# TESTOMATIC-v1_0.net
KiCad netlist of a schematic drawn in EAGLE
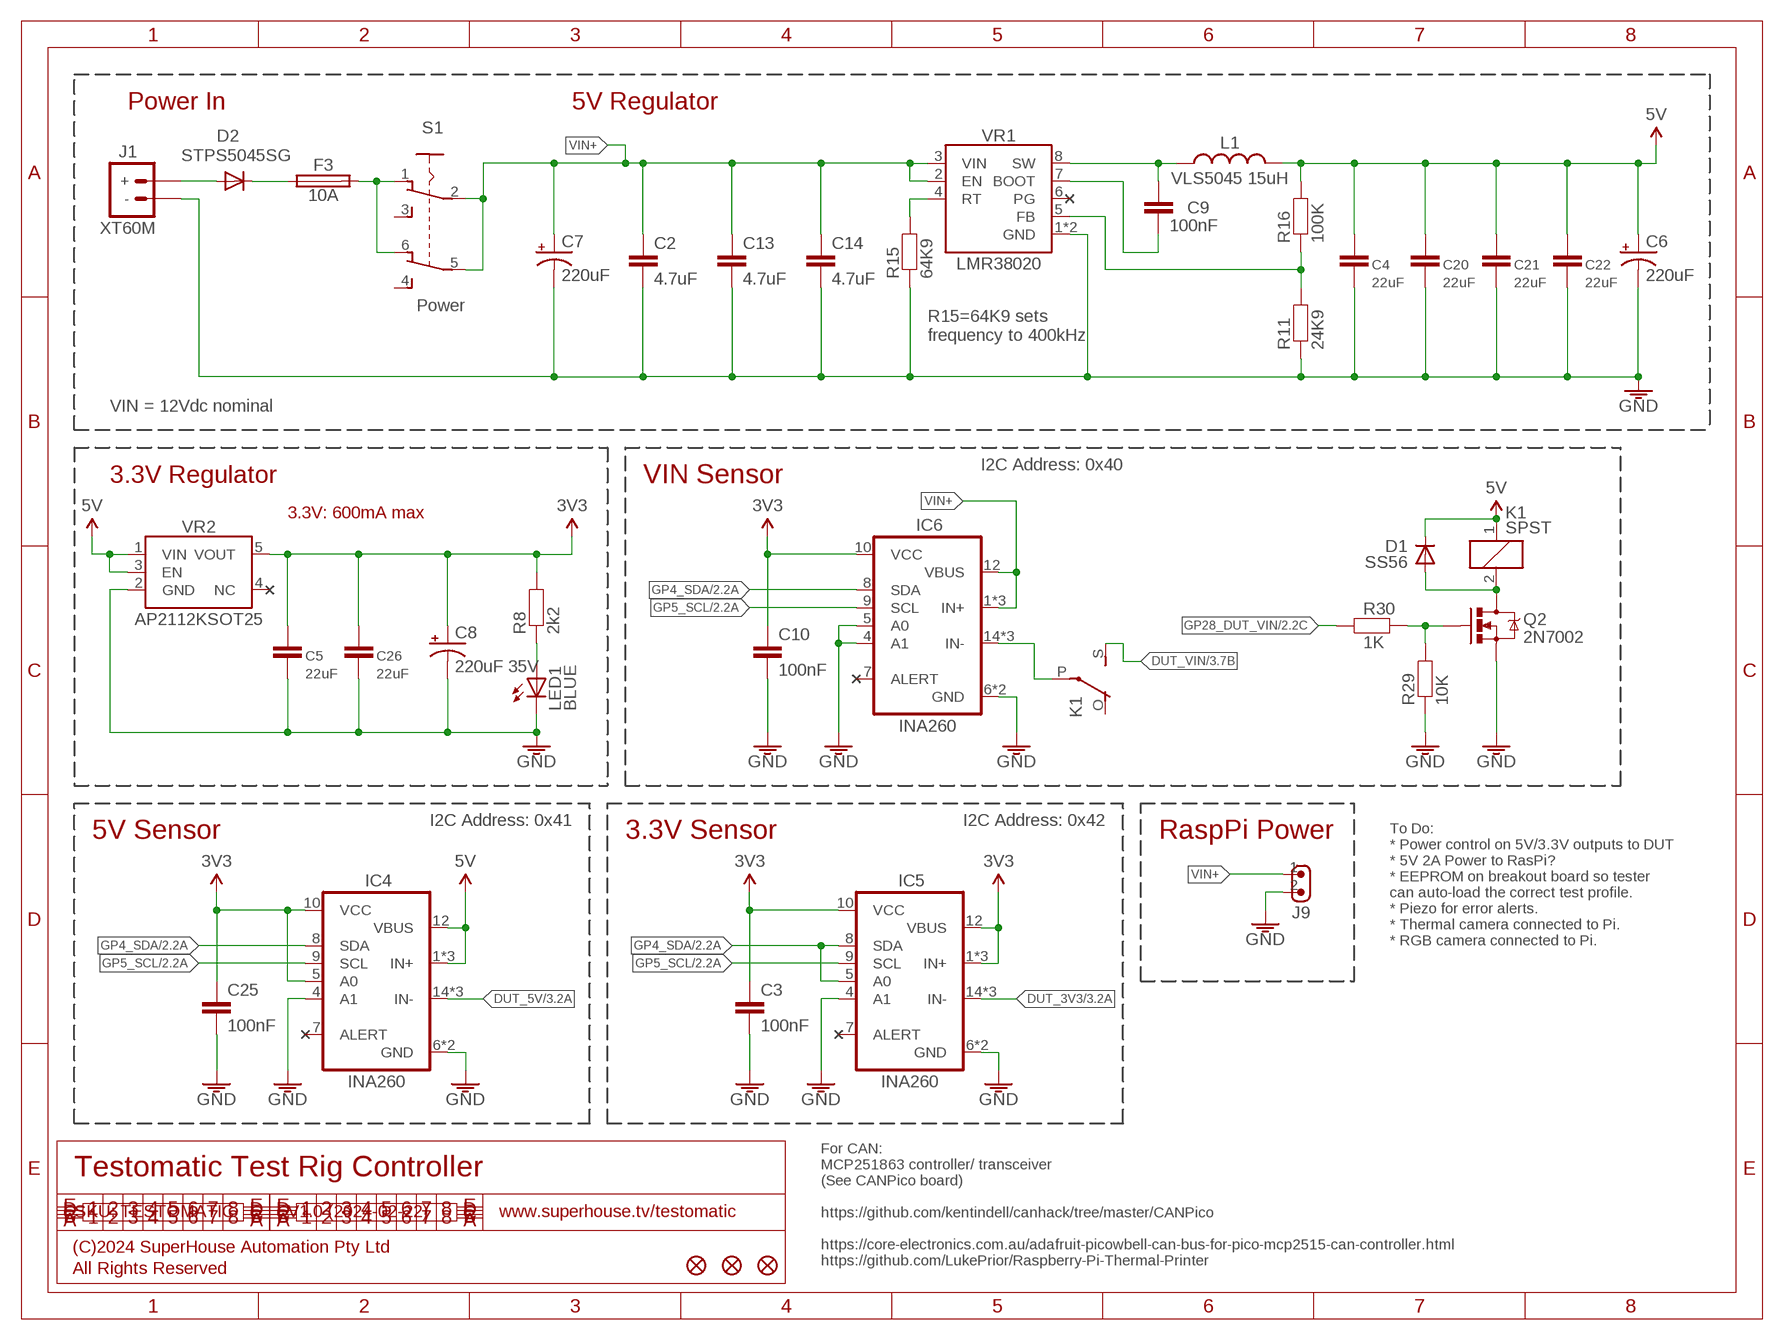
[diagram p0: schematic, sheet 1]
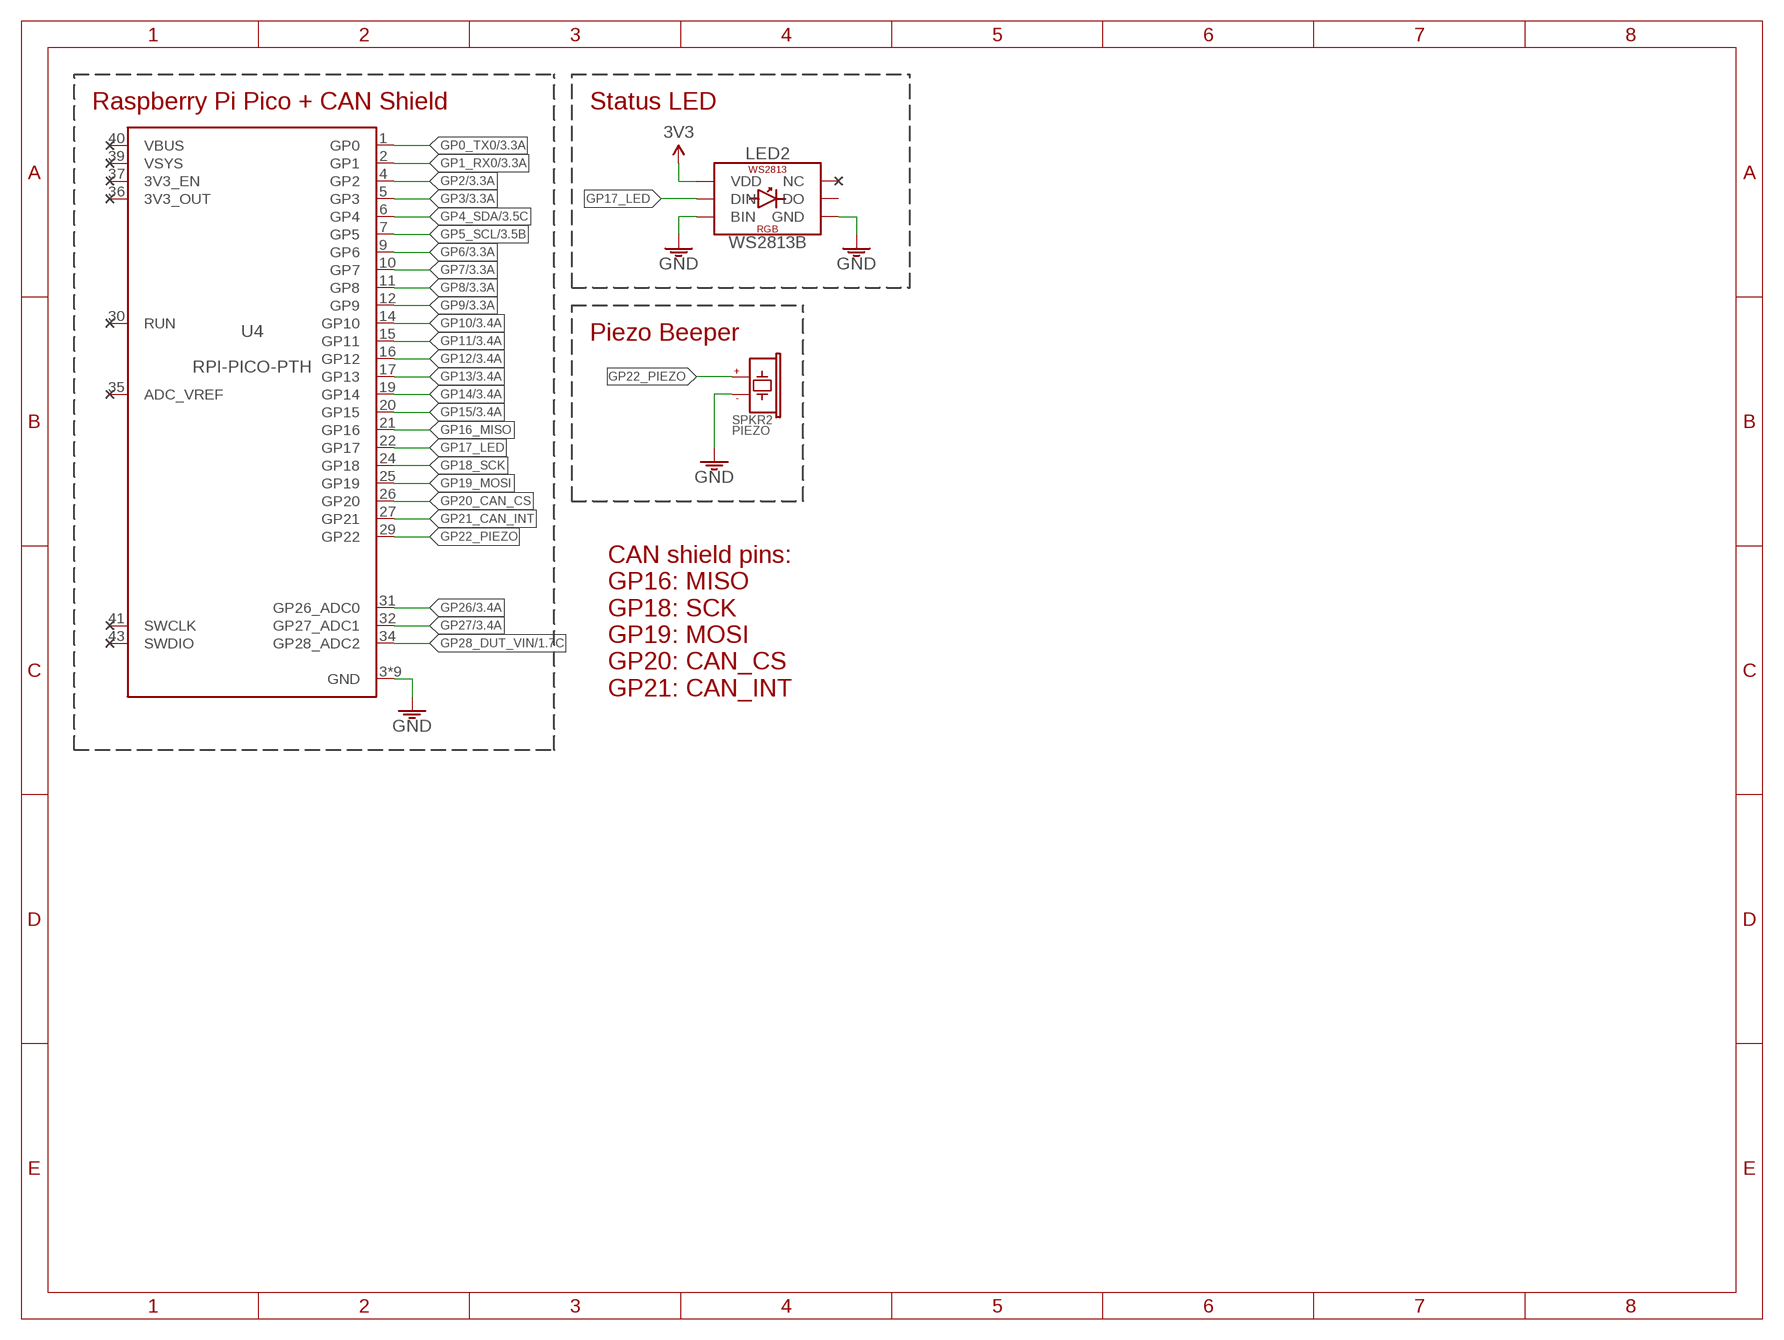
[diagram p1: schematic, sheet 2]
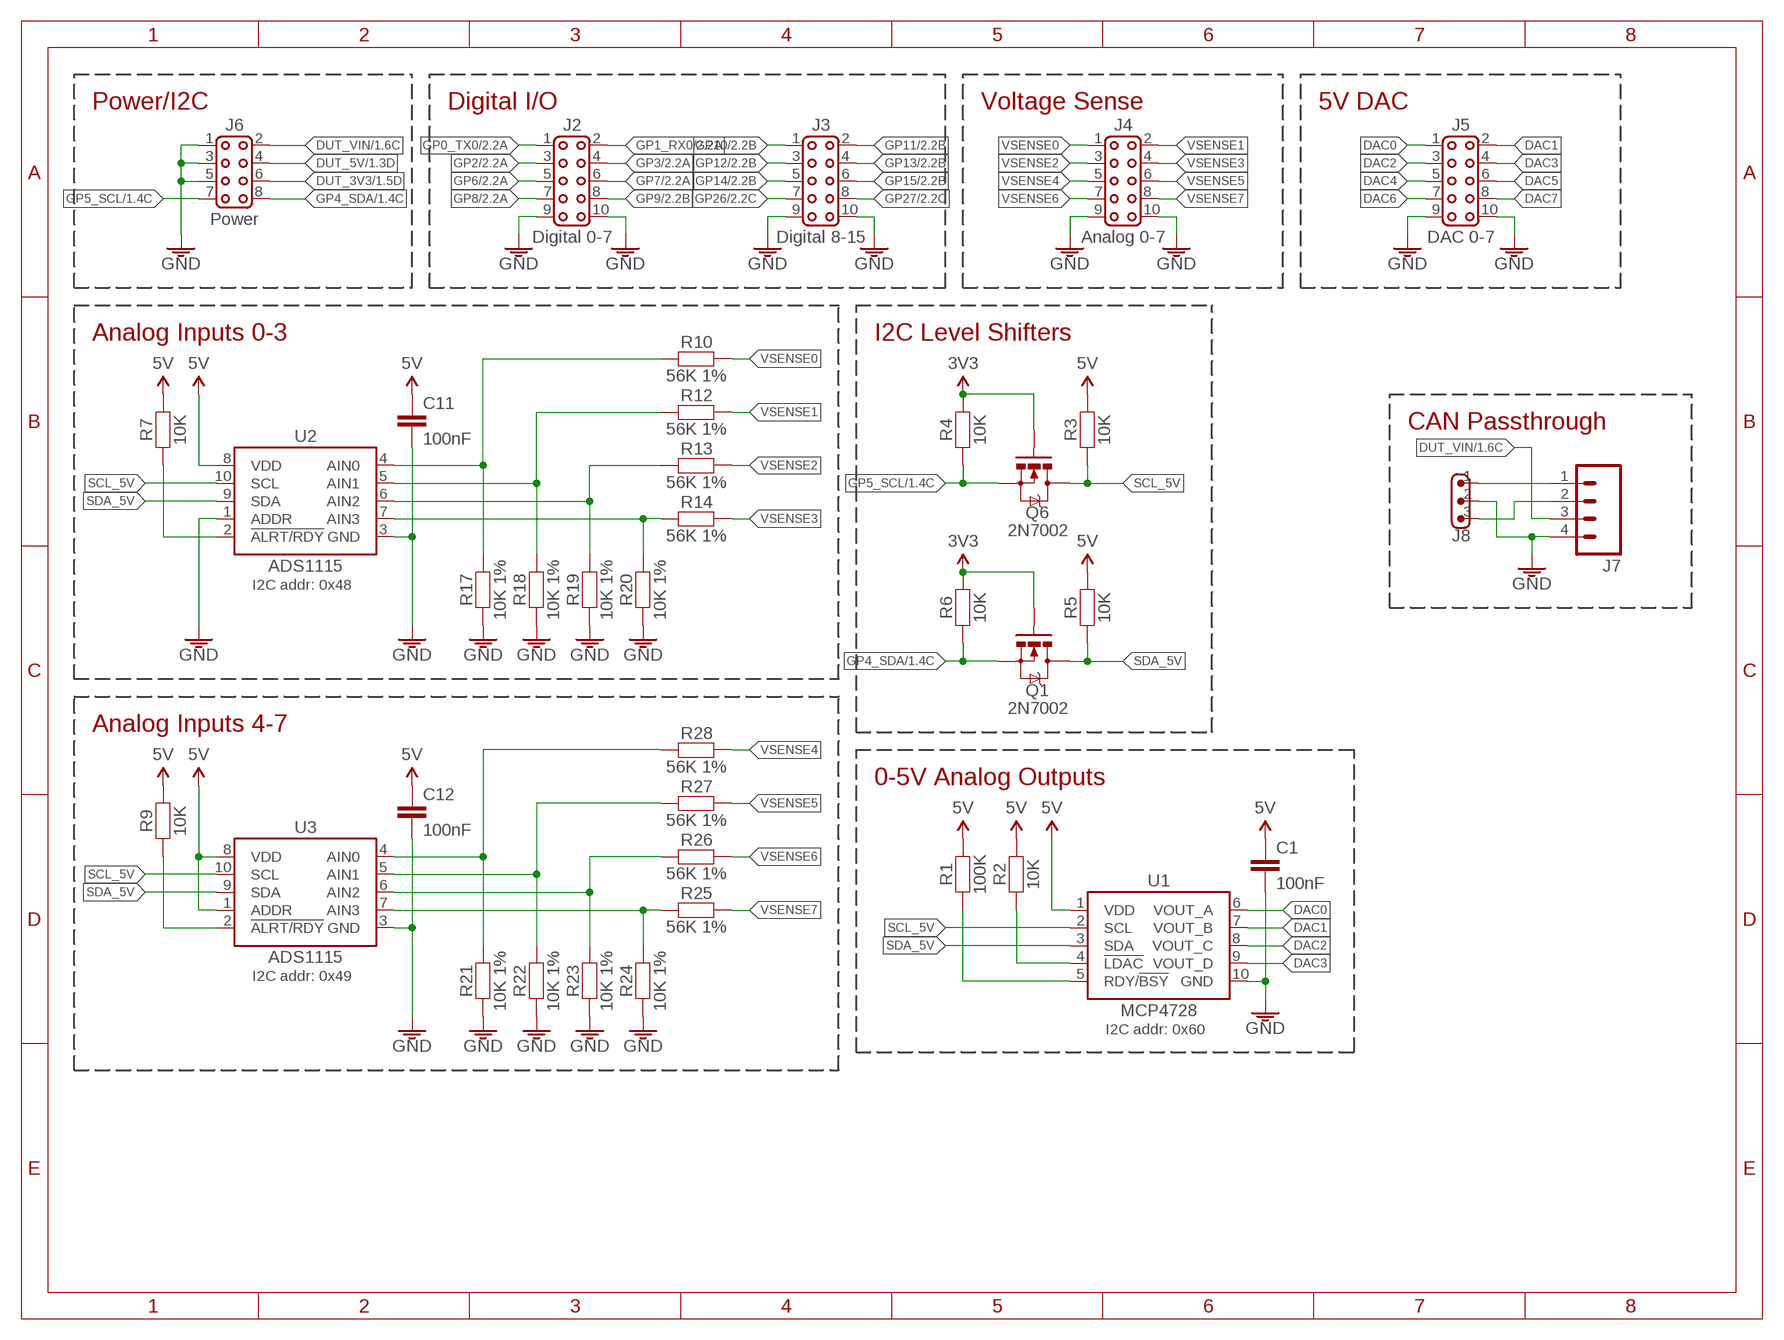
[diagram p2: schematic, sheet 3]

(export (version "E")
  (design (tool "Eeschema 10.0.6"))
  (components
    (comp (ref "C2")
      (value "4.7uF")
      (footprint "eagle-import:C1206")
      (libsource (lib "eagle-import") (part "CAP1206"))
    )
    (comp (ref "C3")
      (value "100nF")
      (footprint "eagle-import:C0603")
      (libsource (lib "eagle-import") (part "CAP0603"))
    )
    (comp (ref "C4")
      (value "22uF")
      (footprint "eagle-import:C0805")
      (libsource (lib "eagle-import") (part "CAP0805"))
    )
    (comp (ref "C5")
      (value "22uF")
      (footprint "eagle-import:C0805")
      (libsource (lib "eagle-import") (part "CAP0805"))
    )
    (comp (ref "C6")
      (value "220uF")
      (footprint "eagle-import:PANASONIC_G")
      (libsource (lib "eagle-import") (part "CAP_POLG"))
    )
    (comp (ref "C7")
      (value "220uF")
      (footprint "eagle-import:PANASONIC_G")
      (libsource (lib "eagle-import") (part "CAP_POLG"))
    )
    (comp (ref "C8")
      (value "220uF 35V")
      (footprint "eagle-import:PANASONIC_G")
      (libsource (lib "eagle-import") (part "CAP_POLG"))
    )
    (comp (ref "C9")
      (value "100nF")
      (footprint "eagle-import:C0603")
      (libsource (lib "eagle-import") (part "CAP0603"))
    )
    (comp (ref "C10")
      (value "100nF")
      (footprint "eagle-import:C0603")
      (libsource (lib "eagle-import") (part "CAP0603"))
    )
    (comp (ref "C13")
      (value "4.7uF")
      (footprint "eagle-import:C1206")
      (libsource (lib "eagle-import") (part "CAP1206"))
    )
    (comp (ref "C14")
      (value "4.7uF")
      (footprint "eagle-import:C1206")
      (libsource (lib "eagle-import") (part "CAP1206"))
    )
    (comp (ref "C20")
      (value "22uF")
      (footprint "eagle-import:C0805")
      (libsource (lib "eagle-import") (part "CAP0805"))
    )
    (comp (ref "C21")
      (value "22uF")
      (footprint "eagle-import:C0805")
      (libsource (lib "eagle-import") (part "CAP0805"))
    )
    (comp (ref "C22")
      (value "22uF")
      (footprint "eagle-import:C0805")
      (libsource (lib "eagle-import") (part "CAP0805"))
    )
    (comp (ref "C25")
      (value "100nF")
      (footprint "eagle-import:C0603")
      (libsource (lib "eagle-import") (part "CAP0603"))
    )
    (comp (ref "C26")
      (value "22uF")
      (footprint "eagle-import:C0805")
      (libsource (lib "eagle-import") (part "CAP0805"))
    )
    (comp (ref "D1")
      (value "SS56")
      (footprint "eagle-import:SMA-DIODE")
      (libsource (lib "eagle-import") (part "DIODESMA"))
    )
    (comp (ref "D2")
      (value "STPS5045SG")
      (footprint "eagle-import:D2PACK")
      (libsource (lib "eagle-import") (part "DIODE-D2PAK"))
    )
    (comp (ref "F3")
      (value "10A")
      (footprint "eagle-import:MCCQ-122")
      (libsource (lib "eagle-import") (part "FUSE-MCCQ"))
    )
    (comp (ref "FID1")
      (value "FIDUCIAL1X2.5")
      (footprint "eagle-import:FIDUCIAL-1X2.5")
      (libsource (lib "eagle-import") (part "FIDUCIAL1X2.5"))
    )
    (comp (ref "FID2")
      (value "FIDUCIAL1X2.5")
      (footprint "eagle-import:FIDUCIAL-1X2.5")
      (libsource (lib "eagle-import") (part "FIDUCIAL1X2.5"))
    )
    (comp (ref "FID3")
      (value "FIDUCIAL1X2.5")
      (footprint "eagle-import:FIDUCIAL-1X2.5")
      (libsource (lib "eagle-import") (part "FIDUCIAL1X2.5"))
    )
    (comp (ref "IC4")
      (value "INA260")
      (footprint "eagle-import:TSSOP-16")
      (libsource (lib "eagle-import") (part "INA260"))
    )
    (comp (ref "IC5")
      (value "INA260")
      (footprint "eagle-import:TSSOP-16")
      (libsource (lib "eagle-import") (part "INA260"))
    )
    (comp (ref "IC6")
      (value "INA260")
      (footprint "eagle-import:TSSOP-16")
      (libsource (lib "eagle-import") (part "INA260"))
    )
    (comp (ref "J1")
      (value "XT60M")
      (footprint "eagle-import:XT60PW-M")
      (libsource (lib "eagle-import") (part "XTXX-60M"))
    )
    (comp (ref "J9")
      (value "M02-SCREW-3.81MM-VERT")
      (footprint "eagle-import:SCREWTERMINAL-3.81MM-VERT-2")
      (libsource (lib "eagle-import") (part "M02-SCREW-3.81MM-VERT"))
    )
    (comp (ref "K1")
      (value "SPST")
      (footprint "eagle-import:G5LE")
      (libsource (lib "eagle-import") (part "SPST"))
    )
    (comp (ref "L1")
      (value "VLS5045 15uH")
      (footprint "eagle-import:INDUCTOR-5045")
      (libsource (lib "eagle-import") (part "INDUCTOR-5045"))
    )
    (comp (ref "LED1")
      (value "BLUE")
      (footprint "eagle-import:LED-0603")
      (libsource (lib "eagle-import") (part "LED0603"))
    )
    (comp (ref "Q2")
      (value "2N7002")
      (footprint "eagle-import:SOT23-3")
      (libsource (lib "eagle-import") (part "MOSFET-NCHANNEL-233"))
    )
    (comp (ref "R8")
      (value "2k2")
      (footprint "eagle-import:R0603")
      (libsource (lib "eagle-import") (part "RESISTOR0603"))
    )
    (comp (ref "R11")
      (value "24K9")
      (footprint "eagle-import:R0603")
      (libsource (lib "eagle-import") (part "RESISTOR0603"))
    )
    (comp (ref "R15")
      (value "64K9")
      (footprint "eagle-import:R0603")
      (libsource (lib "eagle-import") (part "RESISTOR0603"))
    )
    (comp (ref "R16")
      (value "100K")
      (footprint "eagle-import:R0603")
      (libsource (lib "eagle-import") (part "RESISTOR0603"))
    )
    (comp (ref "R29")
      (value "10K")
      (footprint "eagle-import:R0603")
      (libsource (lib "eagle-import") (part "RESISTOR0603"))
    )
    (comp (ref "R30")
      (value "1K")
      (footprint "eagle-import:R0603")
      (libsource (lib "eagle-import") (part "RESISTOR0603"))
    )
    (comp (ref "S1")
      (value "Power")
      (footprint "eagle-import:7201SD9AV2BE")
      (libsource (lib "eagle-import") (part "SWITCH-DPDT3"))
    )
    (comp (ref "VR1")
      (value "LMR38020")
      (footprint "eagle-import:HSOIC8")
      (libsource (lib "eagle-import") (part "LMR38010"))
    )
    (comp (ref "VR2")
      (value "AP2112KSOT25")
      (footprint "eagle-import:SOT23-5")
      (libsource (lib "eagle-import") (part "AP2112KSOT25"))
    )
    (comp (ref "LED2")
      (value "WS2813B")
      (footprint "eagle-import:WS2813")
      (libsource (lib "eagle-import") (part "WS2813-5050"))
    )
    (comp (ref "SPKR2")
      (value "PIEZO")
      (footprint "eagle-import:PIEZO-9.6X9.6-SMT")
      (libsource (lib "eagle-import") (part "PIEZOPOLARISED-SMT"))
    )
    (comp (ref "U4")
      (value "RPI-PICO-PTH")
      (footprint "eagle-import:PICO-PTH")
      (libsource (lib "eagle-import") (part "RPI-PICO-PTH"))
    )
    (comp (ref "C1")
      (value "100nF")
      (footprint "eagle-import:C0603")
      (libsource (lib "eagle-import") (part "CAP0603"))
    )
    (comp (ref "C11")
      (value "100nF")
      (footprint "eagle-import:C0603")
      (libsource (lib "eagle-import") (part "CAP0603"))
    )
    (comp (ref "C12")
      (value "100nF")
      (footprint "eagle-import:C0603")
      (libsource (lib "eagle-import") (part "CAP0603"))
    )
    (comp (ref "J2")
      (value "Digital 0-7")
      (footprint "eagle-import:2X05-2.54-SHROUDED")
      (libsource (lib "eagle-import") (part "M02X5-SHROUDED"))
    )
    (comp (ref "J3")
      (value "Digital 8-15")
      (footprint "eagle-import:2X05-2.54-SHROUDED")
      (libsource (lib "eagle-import") (part "M02X5-SHROUDED"))
    )
    (comp (ref "J4")
      (value "Analog 0-7")
      (footprint "eagle-import:2X05-2.54-SHROUDED")
      (libsource (lib "eagle-import") (part "M02X5-SHROUDED"))
    )
    (comp (ref "J5")
      (value "DAC 0-7")
      (footprint "eagle-import:2X05-2.54-SHROUDED")
      (libsource (lib "eagle-import") (part "M02X5-SHROUDED"))
    )
    (comp (ref "J6")
      (value "Power")
      (footprint "eagle-import:2X04-2.54-SHROUDED")
      (libsource (lib "eagle-import") (part "M02X4-SHROUD"))
    )
    (comp (ref "J7")
      (value "M04-SCREW-3.81MM-VERT-PLUG")
      (footprint "eagle-import:SCREWTERMINAL-3.81MM-VERT-4")
      (libsource (lib "eagle-import") (part "M04-SCREW-3.81MM-VERT-PLUG"))
    )
    (comp (ref "J8")
      (value "M03-SCREW-3.5MM")
      (footprint "eagle-import:SCREWTERMINAL-3.5MM-3")
      (libsource (lib "eagle-import") (part "M03-SCREW-3.5MM"))
    )
    (comp (ref "Q1")
      (value "2N7002")
      (footprint "eagle-import:SOT23-3")
      (libsource (lib "eagle-import") (part "MOSFET-NCHANNEL-233"))
    )
    (comp (ref "Q6")
      (value "2N7002")
      (footprint "eagle-import:SOT23-3")
      (libsource (lib "eagle-import") (part "MOSFET-NCHANNEL-233"))
    )
    (comp (ref "R1")
      (value "100K")
      (footprint "eagle-import:R0603")
      (libsource (lib "eagle-import") (part "RESISTOR0603"))
    )
    (comp (ref "R2")
      (value "10K")
      (footprint "eagle-import:R0603")
      (libsource (lib "eagle-import") (part "RESISTOR0603"))
    )
    (comp (ref "R3")
      (value "10K")
      (footprint "eagle-import:R0603")
      (libsource (lib "eagle-import") (part "RESISTOR0603"))
    )
    (comp (ref "R4")
      (value "10K")
      (footprint "eagle-import:R0603")
      (libsource (lib "eagle-import") (part "RESISTOR0603"))
    )
    (comp (ref "R5")
      (value "10K")
      (footprint "eagle-import:R0603")
      (libsource (lib "eagle-import") (part "RESISTOR0603"))
    )
    (comp (ref "R6")
      (value "10K")
      (footprint "eagle-import:R0603")
      (libsource (lib "eagle-import") (part "RESISTOR0603"))
    )
    (comp (ref "R7")
      (value "10K")
      (footprint "eagle-import:R0603")
      (libsource (lib "eagle-import") (part "RESISTOR0603"))
    )
    (comp (ref "R9")
      (value "10K")
      (footprint "eagle-import:R0603")
      (libsource (lib "eagle-import") (part "RESISTOR0603"))
    )
    (comp (ref "R10")
      (value "56K 1%")
      (footprint "eagle-import:R0603")
      (libsource (lib "eagle-import") (part "RESISTOR0603"))
    )
    (comp (ref "R12")
      (value "56K 1%")
      (footprint "eagle-import:R0603")
      (libsource (lib "eagle-import") (part "RESISTOR0603"))
    )
    (comp (ref "R13")
      (value "56K 1%")
      (footprint "eagle-import:R0603")
      (libsource (lib "eagle-import") (part "RESISTOR0603"))
    )
    (comp (ref "R14")
      (value "56K 1%")
      (footprint "eagle-import:R0603")
      (libsource (lib "eagle-import") (part "RESISTOR0603"))
    )
    (comp (ref "R17")
      (value "10K 1%")
      (footprint "eagle-import:R0603")
      (libsource (lib "eagle-import") (part "RESISTOR0603"))
    )
    (comp (ref "R18")
      (value "10K 1%")
      (footprint "eagle-import:R0603")
      (libsource (lib "eagle-import") (part "RESISTOR0603"))
    )
    (comp (ref "R19")
      (value "10K 1%")
      (footprint "eagle-import:R0603")
      (libsource (lib "eagle-import") (part "RESISTOR0603"))
    )
    (comp (ref "R20")
      (value "10K 1%")
      (footprint "eagle-import:R0603")
      (libsource (lib "eagle-import") (part "RESISTOR0603"))
    )
    (comp (ref "R21")
      (value "10K 1%")
      (footprint "eagle-import:R0603")
      (libsource (lib "eagle-import") (part "RESISTOR0603"))
    )
    (comp (ref "R22")
      (value "10K 1%")
      (footprint "eagle-import:R0603")
      (libsource (lib "eagle-import") (part "RESISTOR0603"))
    )
    (comp (ref "R23")
      (value "10K 1%")
      (footprint "eagle-import:R0603")
      (libsource (lib "eagle-import") (part "RESISTOR0603"))
    )
    (comp (ref "R24")
      (value "10K 1%")
      (footprint "eagle-import:R0603")
      (libsource (lib "eagle-import") (part "RESISTOR0603"))
    )
    (comp (ref "R25")
      (value "56K 1%")
      (footprint "eagle-import:R0603")
      (libsource (lib "eagle-import") (part "RESISTOR0603"))
    )
    (comp (ref "R26")
      (value "56K 1%")
      (footprint "eagle-import:R0603")
      (libsource (lib "eagle-import") (part "RESISTOR0603"))
    )
    (comp (ref "R27")
      (value "56K 1%")
      (footprint "eagle-import:R0603")
      (libsource (lib "eagle-import") (part "RESISTOR0603"))
    )
    (comp (ref "R28")
      (value "56K 1%")
      (footprint "eagle-import:R0603")
      (libsource (lib "eagle-import") (part "RESISTOR0603"))
    )
    (comp (ref "U1")
      (value "MCP4728")
      (footprint "eagle-import:MSOP10")
      (libsource (lib "eagle-import") (part "MCP4728"))
    )
    (comp (ref "U2")
      (value "ADS1115")
      (footprint "eagle-import:MSOP10")
      (libsource (lib "eagle-import") (part "ADS1115"))
    )
    (comp (ref "U3")
      (value "ADS1115")
      (footprint "eagle-import:MSOP10")
      (libsource (lib "eagle-import") (part "ADS1115"))
    )
  )
  (nets
    (net (code "1") (name "3.3V") (class "Default")
      (node (ref "C10") (pin "1") (pinfunction "1_1") (pintype "passive"))
      (node (ref "C25") (pin "1") (pinfunction "1_1") (pintype "passive"))
      (node (ref "C26") (pin "1") (pinfunction "1_1") (pintype "passive"))
      (node (ref "C3") (pin "1") (pinfunction "1_1") (pintype "passive"))
      (node (ref "C5") (pin "1") (pinfunction "1_1") (pintype "passive"))
      (node (ref "C8") (pin "+") (pinfunction "+_+") (pintype "passive"))
      (node (ref "IC4") (pin "10") (pinfunction "VCC_10") (pintype "power_in"))
      (node (ref "IC4") (pin "5") (pinfunction "A0_5") (pintype "input"))
      (node (ref "IC5") (pin "1") (pinfunction "IN+_1") (pintype "input"))
      (node (ref "IC5") (pin "10") (pinfunction "VCC_10") (pintype "power_in"))
      (node (ref "IC5") (pin "12") (pinfunction "VBUS_12") (pintype "input"))
      (node (ref "IC5") (pin "2") (pinfunction "IN+_2") (pintype "input"))
      (node (ref "IC5") (pin "3") (pinfunction "IN+_3") (pintype "input"))
      (node (ref "IC6") (pin "10") (pinfunction "VCC_10") (pintype "power_in"))
      (node (ref "LED2") (pin "2") (pinfunction "VDD_2") (pintype "power_in"))
      (node (ref "Q1") (pin "1") (pinfunction "G_1") (pintype "passive"))
      (node (ref "Q6") (pin "1") (pinfunction "G_1") (pintype "passive"))
      (node (ref "R4") (pin "2") (pinfunction "2_2") (pintype "passive"))
      (node (ref "R6") (pin "2") (pinfunction "2_2") (pintype "passive"))
      (node (ref "R8") (pin "2") (pinfunction "2_2") (pintype "passive"))
      (node (ref "VR2") (pin "5") (pinfunction "VOUT_5") (pintype "bidirectional"))
    )
    (net (code "2") (name "5V") (class "Default")
      (node (ref "C1") (pin "1") (pinfunction "1_1") (pintype "passive"))
      (node (ref "C11") (pin "1") (pinfunction "1_1") (pintype "passive"))
      (node (ref "C12") (pin "1") (pinfunction "1_1") (pintype "passive"))
      (node (ref "C20") (pin "1") (pinfunction "1_1") (pintype "passive"))
      (node (ref "C21") (pin "1") (pinfunction "1_1") (pintype "passive"))
      (node (ref "C22") (pin "1") (pinfunction "1_1") (pintype "passive"))
      (node (ref "C4") (pin "1") (pinfunction "1_1") (pintype "passive"))
      (node (ref "C6") (pin "+") (pinfunction "+_+") (pintype "passive"))
      (node (ref "D1") (pin "C") (pinfunction "C_C") (pintype "passive"))
      (node (ref "IC4") (pin "1") (pinfunction "IN+_1") (pintype "input"))
      (node (ref "IC4") (pin "12") (pinfunction "VBUS_12") (pintype "input"))
      (node (ref "IC4") (pin "2") (pinfunction "IN+_2") (pintype "input"))
      (node (ref "IC4") (pin "3") (pinfunction "IN+_3") (pintype "input"))
      (node (ref "K1") (pin "1") (pinfunction "1_1") (pintype "passive"))
      (node (ref "L1") (pin "2") (pinfunction "2_2") (pintype "passive"))
      (node (ref "R1") (pin "2") (pinfunction "2_2") (pintype "passive"))
      (node (ref "R16") (pin "2") (pinfunction "2_2") (pintype "passive"))
      (node (ref "R2") (pin "2") (pinfunction "2_2") (pintype "passive"))
      (node (ref "R3") (pin "2") (pinfunction "2_2") (pintype "passive"))
      (node (ref "R5") (pin "2") (pinfunction "2_2") (pintype "passive"))
      (node (ref "R7") (pin "2") (pinfunction "2_2") (pintype "passive"))
      (node (ref "R9") (pin "2") (pinfunction "2_2") (pintype "passive"))
      (node (ref "U1") (pin "1") (pinfunction "VDD_1") (pintype "passive"))
      (node (ref "U2") (pin "8") (pinfunction "VDD_8") (pintype "passive"))
      (node (ref "U3") (pin "1") (pinfunction "ADDR_1") (pintype "passive"))
      (node (ref "U3") (pin "8") (pinfunction "VDD_8") (pintype "passive"))
      (node (ref "VR2") (pin "1") (pinfunction "VIN_1") (pintype "bidirectional"))
      (node (ref "VR2") (pin "3") (pinfunction "EN_3") (pintype "bidirectional"))
    )
    (net (code "3") (name "DAC0") (class "Default")
      (node (ref "J5") (pin "1") (pinfunction "1_1") (pintype "passive"))
      (node (ref "U1") (pin "6") (pinfunction "VOUT_A_6") (pintype "passive"))
    )
    (net (code "4") (name "DAC1") (class "Default")
      (node (ref "J5") (pin "2") (pinfunction "2_2") (pintype "passive"))
      (node (ref "U1") (pin "7") (pinfunction "VOUT_B_7") (pintype "passive"))
    )
    (net (code "5") (name "DAC2") (class "Default")
      (node (ref "J5") (pin "3") (pinfunction "3_3") (pintype "passive"))
      (node (ref "U1") (pin "8") (pinfunction "VOUT_C_8") (pintype "passive"))
    )
    (net (code "6") (name "DAC3") (class "Default")
      (node (ref "J5") (pin "4") (pinfunction "4_4") (pintype "passive"))
      (node (ref "U1") (pin "9") (pinfunction "VOUT_D_9") (pintype "passive"))
    )
    (net (code "7") (name "DAC4") (class "Default")
      (node (ref "J5") (pin "5") (pinfunction "5_5") (pintype "passive"))
    )
    (net (code "8") (name "DAC5") (class "Default")
      (node (ref "J5") (pin "6") (pinfunction "6_6") (pintype "passive"))
    )
    (net (code "9") (name "DAC6") (class "Default")
      (node (ref "J5") (pin "7") (pinfunction "7_7") (pintype "passive"))
    )
    (net (code "10") (name "DAC7") (class "Default")
      (node (ref "J5") (pin "8") (pinfunction "8_8") (pintype "passive"))
    )
    (net (code "11") (name "DUT_3V3") (class "Default")
      (node (ref "IC5") (pin "14") (pinfunction "IN-_14") (pintype "input"))
      (node (ref "IC5") (pin "15") (pinfunction "IN-_15") (pintype "input"))
      (node (ref "IC5") (pin "16") (pinfunction "IN-_16") (pintype "input"))
      (node (ref "J6") (pin "6") (pinfunction "6_6") (pintype "passive"))
    )
    (net (code "12") (name "DUT_5V") (class "Default")
      (node (ref "IC4") (pin "14") (pinfunction "IN-_14") (pintype "input"))
      (node (ref "IC4") (pin "15") (pinfunction "IN-_15") (pintype "input"))
      (node (ref "IC4") (pin "16") (pinfunction "IN-_16") (pintype "input"))
      (node (ref "J6") (pin "4") (pinfunction "4_4") (pintype "passive"))
    )
    (net (code "13") (name "DUT_VIN") (class "Default")
      (node (ref "J6") (pin "2") (pinfunction "2_2") (pintype "passive"))
      (node (ref "J7") (pin "3") (pinfunction "3_3") (pintype "passive"))
      (node (ref "K1") (pin "S") (pinfunction "NO_S") (pintype "passive"))
    )
    (net (code "14") (name "GND") (class "Default")
      (node (ref "C1") (pin "2") (pinfunction "2_2") (pintype "passive"))
      (node (ref "C10") (pin "2") (pinfunction "2_2") (pintype "passive"))
      (node (ref "C11") (pin "2") (pinfunction "2_2") (pintype "passive"))
      (node (ref "C12") (pin "2") (pinfunction "2_2") (pintype "passive"))
      (node (ref "C13") (pin "2") (pinfunction "2_2") (pintype "passive"))
      (node (ref "C14") (pin "2") (pinfunction "2_2") (pintype "passive"))
      (node (ref "C2") (pin "2") (pinfunction "2_2") (pintype "passive"))
      (node (ref "C20") (pin "2") (pinfunction "2_2") (pintype "passive"))
      (node (ref "C21") (pin "2") (pinfunction "2_2") (pintype "passive"))
      (node (ref "C22") (pin "2") (pinfunction "2_2") (pintype "passive"))
      (node (ref "C25") (pin "2") (pinfunction "2_2") (pintype "passive"))
      (node (ref "C26") (pin "2") (pinfunction "2_2") (pintype "passive"))
      (node (ref "C3") (pin "2") (pinfunction "2_2") (pintype "passive"))
      (node (ref "C4") (pin "2") (pinfunction "2_2") (pintype "passive"))
      (node (ref "C5") (pin "2") (pinfunction "2_2") (pintype "passive"))
      (node (ref "C6") (pin "-") (pinfunction "-_-") (pintype "passive"))
      (node (ref "C7") (pin "-") (pinfunction "-_-") (pintype "passive"))
      (node (ref "C8") (pin "-") (pinfunction "-_-") (pintype "passive"))
      (node (ref "IC4") (pin "11") (pinfunction "GND_11") (pintype "power_in"))
      (node (ref "IC4") (pin "4") (pinfunction "A1_4") (pintype "input"))
      (node (ref "IC4") (pin "6") (pinfunction "GND_6") (pintype "power_in"))
      (node (ref "IC5") (pin "11") (pinfunction "GND_11") (pintype "power_in"))
      (node (ref "IC5") (pin "4") (pinfunction "A1_4") (pintype "input"))
      (node (ref "IC5") (pin "6") (pinfunction "GND_6") (pintype "power_in"))
      (node (ref "IC6") (pin "11") (pinfunction "GND_11") (pintype "power_in"))
      (node (ref "IC6") (pin "4") (pinfunction "A1_4") (pintype "input"))
      (node (ref "IC6") (pin "5") (pinfunction "A0_5") (pintype "input"))
      (node (ref "IC6") (pin "6") (pinfunction "GND_6") (pintype "power_in"))
      (node (ref "J1") (pin "-") (pinfunction "-_-") (pintype "passive"))
      (node (ref "J2") (pin "10") (pinfunction "10_10") (pintype "passive"))
      (node (ref "J2") (pin "9") (pinfunction "9_9") (pintype "passive"))
      (node (ref "J3") (pin "10") (pinfunction "10_10") (pintype "passive"))
      (node (ref "J3") (pin "9") (pinfunction "9_9") (pintype "passive"))
      (node (ref "J4") (pin "10") (pinfunction "10_10") (pintype "passive"))
      (node (ref "J4") (pin "9") (pinfunction "9_9") (pintype "passive"))
      (node (ref "J5") (pin "10") (pinfunction "10_10") (pintype "passive"))
      (node (ref "J5") (pin "9") (pinfunction "9_9") (pintype "passive"))
      (node (ref "J6") (pin "1") (pinfunction "1_1") (pintype "passive"))
      (node (ref "J6") (pin "3") (pinfunction "3_3") (pintype "passive"))
      (node (ref "J6") (pin "5") (pinfunction "5_5") (pintype "passive"))
      (node (ref "J7") (pin "4") (pinfunction "4_4") (pintype "passive"))
      (node (ref "J8") (pin "2") (pinfunction "2_2") (pintype "passive"))
      (node (ref "J9") (pin "2") (pinfunction "2_2") (pintype "passive"))
      (node (ref "LED1") (pin "C") (pinfunction "C_C") (pintype "passive"))
      (node (ref "LED2") (pin "5") (pinfunction "GND_5") (pintype "power_in"))
      (node (ref "LED2") (pin "6") (pinfunction "BIN_6") (pintype "input"))
      (node (ref "Q2") (pin "2") (pinfunction "S_2") (pintype "passive"))
      (node (ref "R11") (pin "1") (pinfunction "1_1") (pintype "passive"))
      (node (ref "R15") (pin "1") (pinfunction "1_1") (pintype "passive"))
      (node (ref "R17") (pin "1") (pinfunction "1_1") (pintype "passive"))
      (node (ref "R18") (pin "1") (pinfunction "1_1") (pintype "passive"))
      (node (ref "R19") (pin "1") (pinfunction "1_1") (pintype "passive"))
      (node (ref "R20") (pin "1") (pinfunction "1_1") (pintype "passive"))
      (node (ref "R21") (pin "1") (pinfunction "1_1") (pintype "passive"))
      (node (ref "R22") (pin "1") (pinfunction "1_1") (pintype "passive"))
      (node (ref "R23") (pin "1") (pinfunction "1_1") (pintype "passive"))
      (node (ref "R24") (pin "1") (pinfunction "1_1") (pintype "passive"))
      (node (ref "R29") (pin "1") (pinfunction "1_1") (pintype "passive"))
      (node (ref "SPKR2") (pin "2") (pinfunction "-_2") (pintype "bidirectional"))
      (node (ref "U1") (pin "10") (pinfunction "GND_10") (pintype "passive"))
      (node (ref "U2") (pin "1") (pinfunction "ADDR_1") (pintype "passive"))
      (node (ref "U2") (pin "3") (pinfunction "GND_3") (pintype "passive"))
      (node (ref "U3") (pin "3") (pinfunction "GND_3") (pintype "passive"))
      (node (ref "U4") (pin "13") (pinfunction "GND_13") (pintype "power_in"))
      (node (ref "U4") (pin "18") (pinfunction "GND_18") (pintype "power_in"))
      (node (ref "U4") (pin "23") (pinfunction "GND_23") (pintype "power_in"))
      (node (ref "U4") (pin "28") (pinfunction "GND_28") (pintype "power_in"))
      (node (ref "U4") (pin "3") (pinfunction "GND_3") (pintype "power_in"))
      (node (ref "U4") (pin "33") (pinfunction "GND_33") (pintype "power_in"))
      (node (ref "U4") (pin "38") (pinfunction "GND_38") (pintype "power_in"))
      (node (ref "U4") (pin "42") (pinfunction "GND_42") (pintype "power_in"))
      (node (ref "U4") (pin "8") (pinfunction "GND_8") (pintype "power_in"))
      (node (ref "VR1") (pin "1") (pinfunction "GND_1") (pintype "bidirectional"))
      (node (ref "VR1") (pin "TGND") (pinfunction "GND_TGND") (pintype "bidirectional"))
      (node (ref "VR2") (pin "2") (pinfunction "GND_2") (pintype "bidirectional"))
    )
    (net (code "15") (name "GP0_TX0") (class "Default")
      (node (ref "J2") (pin "1") (pinfunction "1_1") (pintype "passive"))
      (node (ref "U4") (pin "1") (pinfunction "GP0_1") (pintype "power_in"))
    )
    (net (code "16") (name "GP1_RX0") (class "Default")
      (node (ref "J2") (pin "2") (pinfunction "2_2") (pintype "passive"))
      (node (ref "U4") (pin "2") (pinfunction "GP1_2") (pintype "power_in"))
    )
    (net (code "17") (name "GP2") (class "Default")
      (node (ref "J2") (pin "3") (pinfunction "3_3") (pintype "passive"))
      (node (ref "U4") (pin "4") (pinfunction "GP2_4") (pintype "power_in"))
    )
    (net (code "18") (name "GP3") (class "Default")
      (node (ref "J2") (pin "4") (pinfunction "4_4") (pintype "passive"))
      (node (ref "U4") (pin "5") (pinfunction "GP3_5") (pintype "bidirectional"))
    )
    (net (code "19") (name "GP4_SDA") (class "Default")
      (node (ref "IC4") (pin "8") (pinfunction "SDA_8") (pintype "bidirectional"))
      (node (ref "IC5") (pin "5") (pinfunction "A0_5") (pintype "input"))
      (node (ref "IC5") (pin "8") (pinfunction "SDA_8") (pintype "bidirectional"))
      (node (ref "IC6") (pin "8") (pinfunction "SDA_8") (pintype "bidirectional"))
      (node (ref "J6") (pin "8") (pinfunction "8_8") (pintype "passive"))
      (node (ref "Q1") (pin "2") (pinfunction "S_2") (pintype "passive"))
      (node (ref "R6") (pin "1") (pinfunction "1_1") (pintype "passive"))
      (node (ref "U4") (pin "6") (pinfunction "GP4_6") (pintype "bidirectional"))
    )
    (net (code "20") (name "GP5_SCL") (class "Default")
      (node (ref "IC4") (pin "9") (pinfunction "SCL_9") (pintype "bidirectional"))
      (node (ref "IC5") (pin "9") (pinfunction "SCL_9") (pintype "bidirectional"))
      (node (ref "IC6") (pin "9") (pinfunction "SCL_9") (pintype "bidirectional"))
      (node (ref "J6") (pin "7") (pinfunction "7_7") (pintype "passive"))
      (node (ref "Q6") (pin "2") (pinfunction "S_2") (pintype "passive"))
      (node (ref "R4") (pin "1") (pinfunction "1_1") (pintype "passive"))
      (node (ref "U4") (pin "7") (pinfunction "GP5_7") (pintype "bidirectional"))
    )
    (net (code "21") (name "GP6") (class "Default")
      (node (ref "J2") (pin "5") (pinfunction "5_5") (pintype "passive"))
      (node (ref "U4") (pin "9") (pinfunction "GP6_9") (pintype "bidirectional"))
    )
    (net (code "22") (name "GP7") (class "Default")
      (node (ref "J2") (pin "6") (pinfunction "6_6") (pintype "passive"))
      (node (ref "U4") (pin "10") (pinfunction "GP7_10") (pintype "bidirectional"))
    )
    (net (code "23") (name "GP8") (class "Default")
      (node (ref "J2") (pin "7") (pinfunction "7_7") (pintype "passive"))
      (node (ref "U4") (pin "11") (pinfunction "GP8_11") (pintype "bidirectional"))
    )
    (net (code "24") (name "GP9") (class "Default")
      (node (ref "J2") (pin "8") (pinfunction "8_8") (pintype "passive"))
      (node (ref "U4") (pin "12") (pinfunction "GP9_12") (pintype "bidirectional"))
    )
    (net (code "25") (name "GP10") (class "Default")
      (node (ref "J3") (pin "1") (pinfunction "1_1") (pintype "passive"))
      (node (ref "U4") (pin "14") (pinfunction "GP10_14") (pintype "bidirectional"))
    )
    (net (code "26") (name "GP11") (class "Default")
      (node (ref "J3") (pin "2") (pinfunction "2_2") (pintype "passive"))
      (node (ref "U4") (pin "15") (pinfunction "GP11_15") (pintype "bidirectional"))
    )
    (net (code "27") (name "GP12") (class "Default")
      (node (ref "J3") (pin "3") (pinfunction "3_3") (pintype "passive"))
      (node (ref "U4") (pin "16") (pinfunction "GP12_16") (pintype "bidirectional"))
    )
    (net (code "28") (name "GP13") (class "Default")
      (node (ref "J3") (pin "4") (pinfunction "4_4") (pintype "passive"))
      (node (ref "U4") (pin "17") (pinfunction "GP13_17") (pintype "bidirectional"))
    )
    (net (code "29") (name "GP14") (class "Default")
      (node (ref "J3") (pin "5") (pinfunction "5_5") (pintype "passive"))
      (node (ref "U4") (pin "19") (pinfunction "GP14_19") (pintype "bidirectional"))
    )
    (net (code "30") (name "GP15") (class "Default")
      (node (ref "J3") (pin "6") (pinfunction "6_6") (pintype "passive"))
      (node (ref "U4") (pin "20") (pinfunction "GP15_20") (pintype "bidirectional"))
    )
    (net (code "31") (name "GP16_MISO") (class "Default")
      (node (ref "U4") (pin "21") (pinfunction "GP16_21") (pintype "power_in"))
    )
    (net (code "32") (name "GP17_LED") (class "Default")
      (node (ref "LED2") (pin "4") (pinfunction "DIN_4") (pintype "input"))
      (node (ref "U4") (pin "22") (pinfunction "GP17_22") (pintype "bidirectional"))
    )
    (net (code "33") (name "GP18_SCK") (class "Default")
      (node (ref "U4") (pin "24") (pinfunction "GP18_24") (pintype "bidirectional"))
    )
    (net (code "34") (name "GP19_MOSI") (class "Default")
      (node (ref "U4") (pin "25") (pinfunction "GP19_25") (pintype "bidirectional"))
    )
    (net (code "35") (name "GP20_CAN_CS") (class "Default")
      (node (ref "U4") (pin "26") (pinfunction "GP20_26") (pintype "bidirectional"))
    )
    (net (code "36") (name "GP21_CAN_INT") (class "Default")
      (node (ref "U4") (pin "27") (pinfunction "GP21_27") (pintype "bidirectional"))
    )
    (net (code "37") (name "GP22_PIEZO") (class "Default")
      (node (ref "SPKR2") (pin "1") (pinfunction "+_1") (pintype "bidirectional"))
      (node (ref "U4") (pin "29") (pinfunction "GP22_29") (pintype "bidirectional"))
    )
    (net (code "38") (name "GP26") (class "Default")
      (node (ref "J3") (pin "7") (pinfunction "7_7") (pintype "passive"))
      (node (ref "U4") (pin "31") (pinfunction "GP26_ADC0_31") (pintype "bidirectional"))
    )
    (net (code "39") (name "GP27") (class "Default")
      (node (ref "J3") (pin "8") (pinfunction "8_8") (pintype "passive"))
      (node (ref "U4") (pin "32") (pinfunction "GP27_ADC1_32") (pintype "bidirectional"))
    )
    (net (code "40") (name "GP28_DUT_VIN") (class "Default")
      (node (ref "R30") (pin "1") (pinfunction "1_1") (pintype "passive"))
      (node (ref "U4") (pin "34") (pinfunction "GP28_ADC2_34") (pintype "bidirectional"))
    )
    (net (code "41") (name "Net-(D2-A-Pad1)") (class "Default")
      (node (ref "D2") (pin "1") (pinfunction "A_1") (pintype "passive"))
      (node (ref "D2") (pin "3") (pinfunction "A_3") (pintype "passive"))
      (node (ref "J1") (pin "+") (pinfunction "+_+") (pintype "passive"))
    )
    (net (code "42") (name "Net-(D2-C)") (class "Default")
      (node (ref "D2") (pin "2") (pinfunction "C_2") (pintype "passive"))
      (node (ref "F3") (pin "1") (pinfunction "1_1") (pintype "passive"))
      (node (ref "F3") (pin "2") (pinfunction "1_2") (pintype "passive"))
    )
    (net (code "43") (name "Net-(F3-2-Pad3)") (class "Default")
      (node (ref "F3") (pin "3") (pinfunction "2_3") (pintype "passive"))
      (node (ref "F3") (pin "4") (pinfunction "2_4") (pintype "passive"))
      (node (ref "S1") (pin "1") (pinfunction "1_1") (pintype "passive"))
      (node (ref "S1") (pin "6") (pinfunction "6_6") (pintype "passive"))
    )
    (net (code "44") (name "Net-(J7-Pad1)") (class "Default")
      (node (ref "J7") (pin "1") (pinfunction "1_1") (pintype "passive"))
      (node (ref "J8") (pin "1") (pinfunction "1_1") (pintype "passive"))
    )
    (net (code "45") (name "Net-(J7-Pad2)") (class "Default")
      (node (ref "J7") (pin "2") (pinfunction "2_2") (pintype "passive"))
      (node (ref "J8") (pin "3") (pinfunction "3_3") (pintype "passive"))
    )
    (net (code "46") (name "Net-(K1B-COM)") (class "Default")
      (node (ref "IC6") (pin "14") (pinfunction "IN-_14") (pintype "input"))
      (node (ref "IC6") (pin "15") (pinfunction "IN-_15") (pintype "input"))
      (node (ref "IC6") (pin "16") (pinfunction "IN-_16") (pintype "input"))
      (node (ref "K1") (pin "P") (pinfunction "COM_P") (pintype "passive"))
    )
    (net (code "47") (name "Net-(LED1-PadA)") (class "Default")
      (node (ref "LED1") (pin "A") (pinfunction "A_A") (pintype "passive"))
      (node (ref "R8") (pin "1") (pinfunction "1_1") (pintype "passive"))
    )
    (net (code "48") (name "Net-(Q2-D)") (class "Default")
      (node (ref "D1") (pin "A") (pinfunction "A_A") (pintype "passive"))
      (node (ref "K1") (pin "2") (pinfunction "2_2") (pintype "passive"))
      (node (ref "Q2") (pin "3") (pinfunction "D_3") (pintype "passive"))
    )
    (net (code "49") (name "Net-(Q2-G)") (class "Default")
      (node (ref "Q2") (pin "1") (pinfunction "G_1") (pintype "passive"))
      (node (ref "R29") (pin "2") (pinfunction "2_2") (pintype "passive"))
      (node (ref "R30") (pin "2") (pinfunction "2_2") (pintype "passive"))
    )
    (net (code "50") (name "Net-(U1-RDY{slash}~{BSY})") (class "Default")
      (node (ref "R1") (pin "1") (pinfunction "1_1") (pintype "passive"))
      (node (ref "U1") (pin "5") (pinfunction "RDY/~{BSY}_5") (pintype "passive"))
    )
    (net (code "51") (name "Net-(U1-~{LDAC})") (class "Default")
      (node (ref "R2") (pin "1") (pinfunction "1_1") (pintype "passive"))
      (node (ref "U1") (pin "4") (pinfunction "~{LDAC}_4") (pintype "passive"))
    )
    (net (code "52") (name "Net-(U2-AIN0)") (class "Default")
      (node (ref "R10") (pin "1") (pinfunction "1_1") (pintype "passive"))
      (node (ref "R17") (pin "2") (pinfunction "2_2") (pintype "passive"))
      (node (ref "U2") (pin "4") (pinfunction "AIN0_4") (pintype "passive"))
    )
    (net (code "53") (name "Net-(U2-AIN1)") (class "Default")
      (node (ref "R12") (pin "1") (pinfunction "1_1") (pintype "passive"))
      (node (ref "R18") (pin "2") (pinfunction "2_2") (pintype "passive"))
      (node (ref "U2") (pin "5") (pinfunction "AIN1_5") (pintype "passive"))
    )
    (net (code "54") (name "Net-(U2-AIN2)") (class "Default")
      (node (ref "R13") (pin "1") (pinfunction "1_1") (pintype "passive"))
      (node (ref "R19") (pin "2") (pinfunction "2_2") (pintype "passive"))
      (node (ref "U2") (pin "6") (pinfunction "AIN2_6") (pintype "passive"))
    )
    (net (code "55") (name "Net-(U2-AIN3)") (class "Default")
      (node (ref "R14") (pin "1") (pinfunction "1_1") (pintype "passive"))
      (node (ref "R20") (pin "2") (pinfunction "2_2") (pintype "passive"))
      (node (ref "U2") (pin "7") (pinfunction "AIN3_7") (pintype "passive"))
    )
    (net (code "56") (name "Net-(U2-~{ALRT{slash}RDY})") (class "Default")
      (node (ref "R7") (pin "1") (pinfunction "1_1") (pintype "passive"))
      (node (ref "U2") (pin "2") (pinfunction "~{ALRT/RDY}_2") (pintype "passive"))
    )
    (net (code "57") (name "Net-(U3-AIN0)") (class "Default")
      (node (ref "R21") (pin "2") (pinfunction "2_2") (pintype "passive"))
      (node (ref "R28") (pin "1") (pinfunction "1_1") (pintype "passive"))
      (node (ref "U3") (pin "4") (pinfunction "AIN0_4") (pintype "passive"))
    )
    (net (code "58") (name "Net-(U3-AIN1)") (class "Default")
      (node (ref "R22") (pin "2") (pinfunction "2_2") (pintype "passive"))
      (node (ref "R27") (pin "1") (pinfunction "1_1") (pintype "passive"))
      (node (ref "U3") (pin "5") (pinfunction "AIN1_5") (pintype "passive"))
    )
    (net (code "59") (name "Net-(U3-AIN2)") (class "Default")
      (node (ref "R23") (pin "2") (pinfunction "2_2") (pintype "passive"))
      (node (ref "R26") (pin "1") (pinfunction "1_1") (pintype "passive"))
      (node (ref "U3") (pin "6") (pinfunction "AIN2_6") (pintype "passive"))
    )
    (net (code "60") (name "Net-(U3-AIN3)") (class "Default")
      (node (ref "R24") (pin "2") (pinfunction "2_2") (pintype "passive"))
      (node (ref "R25") (pin "1") (pinfunction "1_1") (pintype "passive"))
      (node (ref "U3") (pin "7") (pinfunction "AIN3_7") (pintype "passive"))
    )
    (net (code "61") (name "Net-(U3-~{ALRT{slash}RDY})") (class "Default")
      (node (ref "R9") (pin "1") (pinfunction "1_1") (pintype "passive"))
      (node (ref "U3") (pin "2") (pinfunction "~{ALRT/RDY}_2") (pintype "passive"))
    )
    (net (code "62") (name "Net-(VR1-BOOT)") (class "Default")
      (node (ref "C9") (pin "2") (pinfunction "2_2") (pintype "passive"))
      (node (ref "VR1") (pin "7") (pinfunction "BOOT_7") (pintype "bidirectional"))
    )
    (net (code "63") (name "Net-(VR1-FB)") (class "Default")
      (node (ref "R11") (pin "2") (pinfunction "2_2") (pintype "passive"))
      (node (ref "R16") (pin "1") (pinfunction "1_1") (pintype "passive"))
      (node (ref "VR1") (pin "5") (pinfunction "FB_5") (pintype "power_in"))
    )
    (net (code "64") (name "Net-(VR1-RT)") (class "Default")
      (node (ref "R15") (pin "2") (pinfunction "2_2") (pintype "passive"))
      (node (ref "VR1") (pin "4") (pinfunction "RT_4") (pintype "power_in"))
    )
    (net (code "65") (name "Net-(VR1-SW)") (class "Default")
      (node (ref "C9") (pin "1") (pinfunction "1_1") (pintype "passive"))
      (node (ref "L1") (pin "1") (pinfunction "1_1") (pintype "passive"))
      (node (ref "VR1") (pin "8") (pinfunction "SW_8") (pintype "bidirectional"))
    )
    (net (code "66") (name "PG") (class "Default")
      (node (ref "VR1") (pin "6") (pinfunction "PG_6") (pintype "power_in"))
    )
    (net (code "67") (name "SCL_5V") (class "Default")
      (node (ref "Q6") (pin "3") (pinfunction "D_3") (pintype "passive"))
      (node (ref "R3") (pin "1") (pinfunction "1_1") (pintype "passive"))
      (node (ref "U1") (pin "2") (pinfunction "SCL_2") (pintype "passive"))
      (node (ref "U2") (pin "10") (pinfunction "SCL_10") (pintype "passive"))
      (node (ref "U3") (pin "10") (pinfunction "SCL_10") (pintype "passive"))
    )
    (net (code "68") (name "SDA_5V") (class "Default")
      (node (ref "Q1") (pin "3") (pinfunction "D_3") (pintype "passive"))
      (node (ref "R5") (pin "1") (pinfunction "1_1") (pintype "passive"))
      (node (ref "U1") (pin "3") (pinfunction "SDA_3") (pintype "passive"))
      (node (ref "U2") (pin "9") (pinfunction "SDA_9") (pintype "passive"))
      (node (ref "U3") (pin "9") (pinfunction "SDA_9") (pintype "passive"))
    )
    (net (code "69") (name "VBUS") (class "Default")
      (node (ref "U4") (pin "40") (pinfunction "VBUS_40") (pintype "power_in"))
    )
    (net (code "70") (name "VIN+") (class "Default")
      (node (ref "C13") (pin "1") (pinfunction "1_1") (pintype "passive"))
      (node (ref "C14") (pin "1") (pinfunction "1_1") (pintype "passive"))
      (node (ref "C2") (pin "1") (pinfunction "1_1") (pintype "passive"))
      (node (ref "C7") (pin "+") (pinfunction "+_+") (pintype "passive"))
      (node (ref "IC6") (pin "1") (pinfunction "IN+_1") (pintype "input"))
      (node (ref "IC6") (pin "12") (pinfunction "VBUS_12") (pintype "input"))
      (node (ref "IC6") (pin "2") (pinfunction "IN+_2") (pintype "input"))
      (node (ref "IC6") (pin "3") (pinfunction "IN+_3") (pintype "input"))
      (node (ref "J9") (pin "1") (pinfunction "1_1") (pintype "passive"))
      (node (ref "S1") (pin "2") (pinfunction "2_2") (pintype "passive"))
      (node (ref "S1") (pin "5") (pinfunction "5_5") (pintype "passive"))
      (node (ref "VR1") (pin "2") (pinfunction "EN_2") (pintype "power_in"))
      (node (ref "VR1") (pin "3") (pinfunction "VIN_3") (pintype "power_in"))
    )
    (net (code "71") (name "VSENSE0") (class "Default")
      (node (ref "J4") (pin "1") (pinfunction "1_1") (pintype "passive"))
      (node (ref "R10") (pin "2") (pinfunction "2_2") (pintype "passive"))
    )
    (net (code "72") (name "VSENSE1") (class "Default")
      (node (ref "J4") (pin "2") (pinfunction "2_2") (pintype "passive"))
      (node (ref "R12") (pin "2") (pinfunction "2_2") (pintype "passive"))
    )
    (net (code "73") (name "VSENSE2") (class "Default")
      (node (ref "J4") (pin "3") (pinfunction "3_3") (pintype "passive"))
      (node (ref "R13") (pin "2") (pinfunction "2_2") (pintype "passive"))
    )
    (net (code "74") (name "VSENSE3") (class "Default")
      (node (ref "J4") (pin "4") (pinfunction "4_4") (pintype "passive"))
      (node (ref "R14") (pin "2") (pinfunction "2_2") (pintype "passive"))
    )
    (net (code "75") (name "VSENSE4") (class "Default")
      (node (ref "J4") (pin "5") (pinfunction "5_5") (pintype "passive"))
      (node (ref "R28") (pin "2") (pinfunction "2_2") (pintype "passive"))
    )
    (net (code "76") (name "VSENSE5") (class "Default")
      (node (ref "J4") (pin "6") (pinfunction "6_6") (pintype "passive"))
      (node (ref "R27") (pin "2") (pinfunction "2_2") (pintype "passive"))
    )
    (net (code "77") (name "VSENSE6") (class "Default")
      (node (ref "J4") (pin "7") (pinfunction "7_7") (pintype "passive"))
      (node (ref "R26") (pin "2") (pinfunction "2_2") (pintype "passive"))
    )
    (net (code "78") (name "VSENSE7") (class "Default")
      (node (ref "J4") (pin "8") (pinfunction "8_8") (pintype "passive"))
      (node (ref "R25") (pin "2") (pinfunction "2_2") (pintype "passive"))
    )
    (net (code "79") (name "unconnected-(IC4-ALERT-Pad7)") (class "Default")
      (node (ref "IC4") (pin "7") (pinfunction "ALERT_7") (pintype "input"))
    )
    (net (code "80") (name "unconnected-(IC5-ALERT-Pad7)") (class "Default")
      (node (ref "IC5") (pin "7") (pinfunction "ALERT_7") (pintype "input"))
    )
    (net (code "81") (name "unconnected-(IC6-ALERT-Pad7)") (class "Default")
      (node (ref "IC6") (pin "7") (pinfunction "ALERT_7") (pintype "input"))
    )
    (net (code "82") (name "unconnected-(K1B-NC-PadO)") (class "Default")
      (node (ref "K1") (pin "O") (pinfunction "NC_O") (pintype "passive"))
    )
    (net (code "83") (name "unconnected-(LED2-DO-Pad3)") (class "Default")
      (node (ref "LED2") (pin "3") (pinfunction "DO_3") (pintype "output"))
    )
    (net (code "84") (name "unconnected-(LED2-NC-Pad1)") (class "Default")
      (node (ref "LED2") (pin "1") (pinfunction "NC_1") (pintype "no_connect"))
    )
    (net (code "85") (name "unconnected-(S1-Pad3)") (class "Default")
      (node (ref "S1") (pin "3") (pinfunction "3_3") (pintype "passive"))
    )
    (net (code "86") (name "unconnected-(S1-Pad4)") (class "Default")
      (node (ref "S1") (pin "4") (pinfunction "4_4") (pintype "passive"))
    )
    (net (code "87") (name "unconnected-(U4-3V3_EN-Pad37)") (class "Default")
      (node (ref "U4") (pin "37") (pinfunction "3V3_EN_37") (pintype "bidirectional"))
    )
    (net (code "88") (name "unconnected-(U4-3V3_OUT-Pad36)") (class "Default")
      (node (ref "U4") (pin "36") (pinfunction "3V3_OUT_36") (pintype "bidirectional"))
    )
    (net (code "89") (name "unconnected-(U4-ADC_VREF-Pad35)") (class "Default")
      (node (ref "U4") (pin "35") (pinfunction "ADC_VREF_35") (pintype "bidirectional"))
    )
    (net (code "90") (name "unconnected-(U4-RUN-Pad30)") (class "Default")
      (node (ref "U4") (pin "30") (pinfunction "RUN_30") (pintype "bidirectional"))
    )
    (net (code "91") (name "unconnected-(U4-SWCLK-Pad41)") (class "Default")
      (node (ref "U4") (pin "41") (pinfunction "SWCLK_41") (pintype "bidirectional"))
    )
    (net (code "92") (name "unconnected-(U4-SWDIO-Pad43)") (class "Default")
      (node (ref "U4") (pin "43") (pinfunction "SWDIO_43") (pintype "bidirectional"))
    )
    (net (code "93") (name "unconnected-(U4-VSYS-Pad39)") (class "Default")
      (node (ref "U4") (pin "39") (pinfunction "VSYS_39") (pintype "bidirectional"))
    )
    (net (code "94") (name "unconnected-(VR2-NC-Pad4)") (class "Default")
      (node (ref "VR2") (pin "4") (pinfunction "NC_4") (pintype "bidirectional"))
    )
  )
)
